# 08_PX4IO_V2.net
KiCad netlist of a schematic drawn in Altium Designer
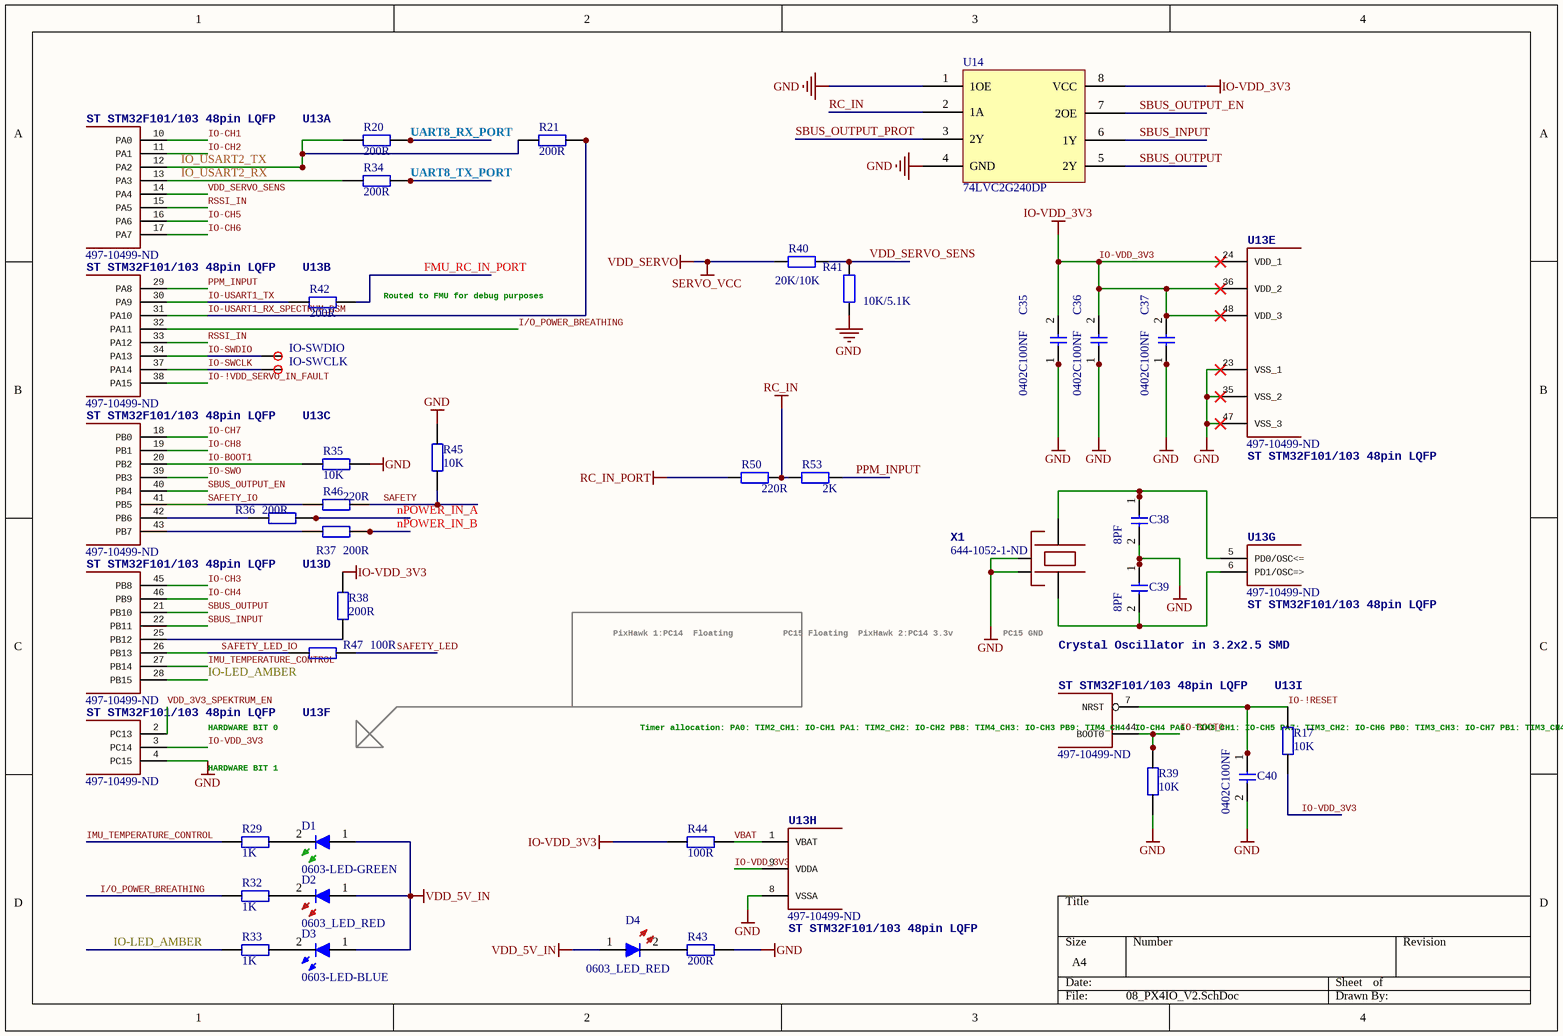
[diagram p0: 08_PX4IO_V2.SchDoc]

(export (version "E")
  (design (tool "Eeschema 10.0.6"))
  (components
    (comp (ref "C35")
      (value "0402C100NF")
      (footprint "0402C")
      (description "50V 5%")
      (libsource (lib "CUAV") (part "0402C100NF"))
    )
    (comp (ref "C36")
      (value "0402C100NF")
      (footprint "0402C")
      (description "50V 5%")
      (libsource (lib "CUAV") (part "0402C100NF"))
    )
    (comp (ref "C37")
      (value "0402C100NF")
      (footprint "0402C")
      (description "50V 5%")
      (libsource (lib "CUAV") (part "0402C100NF"))
    )
    (comp (ref "C38")
      (value "8PF")
      (footprint "0402C")
      (description "50V 5%")
      (libsource (lib "CUAV") (part "0402C100NF"))
    )
    (comp (ref "C39")
      (value "8PF")
      (footprint "0402C")
      (description "50V 5%")
      (libsource (lib "CUAV") (part "0402C100NF"))
    )
    (comp (ref "C40")
      (value "0402C100NF")
      (footprint "0402C")
      (description "50V 5%")
      (libsource (lib "CUAV") (part "0402C100NF"))
    )
    (comp (ref "D1")
      (value "0603-LED-GREEN")
      (footprint "0603-LED-Green")
      (libsource (lib "CUAV") (part "0603-LED-GREEN"))
    )
    (comp (ref "D2")
      (value "0603_LED_RED")
      (footprint "0603-LED-RED")
      (libsource (lib "CUAV") (part "0603_LED_RED"))
    )
    (comp (ref "D3")
      (value "0603-LED-BLUE")
      (footprint "0603-LED-blue")
      (libsource (lib "CUAV") (part "0603-LED-BLUE"))
    )
    (comp (ref "D4")
      (value "0603_LED_RED")
      (footprint "0603-LED-RED")
      (libsource (lib "CUAV") (part "0603_LED_RED"))
    )
    (comp (ref "IO-SWCLK")
      (value "TP_0.75")
      (footprint "TP0.75")
      (description "TP_0.75MM")
      (libsource (lib "CUAV") (part "TP_0.75"))
    )
    (comp (ref "IO-SWDIO")
      (value "TP_0.75")
      (footprint "TP0.75")
      (description "TP_0.75MM")
      (libsource (lib "CUAV") (part "TP_0.75"))
    )
    (comp (ref "R17")
      (value "10K")
      (footprint "0402R")
      (description "0402R1K 1%")
      (libsource (lib "") (part "0402R1K_3"))
    )
    (comp (ref "R20")
      (value "200R")
      (footprint "0402R")
      (description "0402R1K 1%")
      (libsource (lib "CUAV") (part "0402R1K"))
    )
    (comp (ref "R21")
      (value "200R")
      (footprint "0402R")
      (description "0402R1K 1%")
      (libsource (lib "CUAV") (part "0402R1K"))
    )
    (comp (ref "R29")
      (value "1K")
      (footprint "0402R")
      (description "0402R1K 1%")
      (libsource (lib "CUAV") (part "0402R1K"))
    )
    (comp (ref "R32")
      (value "1K")
      (footprint "0402R")
      (description "0402R1K 1%")
      (libsource (lib "CUAV") (part "0402R1K"))
    )
    (comp (ref "R33")
      (value "1K")
      (footprint "0402R")
      (description "0402R1K 1%")
      (libsource (lib "CUAV") (part "0402R1K"))
    )
    (comp (ref "R34")
      (value "200R")
      (footprint "0402R")
      (description "0402R1K 1%")
      (libsource (lib "CUAV") (part "0402R1K"))
    )
    (comp (ref "R35")
      (value "10K")
      (footprint "0402R")
      (description "0402R1K 1%")
      (libsource (lib "CUAV") (part "0402R1K"))
    )
    (comp (ref "R36")
      (value "200R")
      (footprint "0402R")
      (description "0402R1K 1%")
      (libsource (lib "CUAV") (part "0402R1K"))
    )
    (comp (ref "R37")
      (value "200R")
      (footprint "0402R")
      (description "0402R1K 1%")
      (libsource (lib "CUAV") (part "0402R1K"))
    )
    (comp (ref "R38")
      (value "200R")
      (footprint "0402R")
      (description "0402R1K 1%")
      (libsource (lib "") (part "0402R1K_2"))
    )
    (comp (ref "R39")
      (value "10K")
      (footprint "0402R")
      (description "0402R1K 1%")
      (libsource (lib "") (part "0402R1K_2"))
    )
    (comp (ref "R40")
      (value "20K/10K")
      (description "Resistor")
      (fields (field (name "PUBLISHER") "Altium Limited"))
      (libsource (lib "Miscellaneous Devices") (part "Res2"))
    )
    (comp (ref "R41")
      (value "10K/5.1K")
      (description "Resistor")
      (fields (field (name "PUBLISHER") "Altium Limited"))
      (libsource (lib "") (part "Res2_1"))
    )
    (comp (ref "R42")
      (value "200R")
      (footprint "0402R")
      (description "0402R1K 1%")
      (libsource (lib "CUAV") (part "0402R1K"))
    )
    (comp (ref "R43")
      (value "200R")
      (footprint "0402R")
      (description "0402R1K 1%")
      (libsource (lib "CUAV") (part "0402R1K"))
    )
    (comp (ref "R44")
      (value "100R")
      (footprint "0402R")
      (description "0402R1K 1%")
      (libsource (lib "CUAV") (part "0402R1K"))
    )
    (comp (ref "R45")
      (value "10K")
      (footprint "0402R")
      (description "0402R1K 1%")
      (libsource (lib "") (part "0402R1K_2"))
    )
    (comp (ref "R46")
      (value "220R")
      (footprint "0402R")
      (description "0402R1K 1%")
      (libsource (lib "") (part "0402R1K_1"))
    )
    (comp (ref "R47")
      (value "100R")
      (footprint "0402R")
      (description "0402R1K 1%")
      (libsource (lib "") (part "0402R1K_1"))
    )
    (comp (ref "R50")
      (value "220R")
      (description "Resistor")
      (fields (field (name "PUBLISHER") "Altium Limited"))
      (libsource (lib "Miscellaneous Devices") (part "Res2"))
    )
    (comp (ref "R53")
      (value "2K")
      (description "Resistor")
      (fields (field (name "PUBLISHER") "Altium Limited"))
      (libsource (lib "Miscellaneous Devices") (part "Res2"))
    )
    (comp (ref "U13")
      (value "ST STM32F101/103 48pin LQFP")
      (footprint "TQFP48")
      (description "MCU 32BIT ARM 64K FLASH 48LQFP")
      (fields (field (name "SUPPLIER PART NUMBER 1") "497-10499-ND") (field (name "3DR_PARTNO") "EMC0842"))
      (libsource (lib "pixhawk2") (part "STM32F10XCXT6"))
    )
    (comp (ref "U14")
      (value "74LVC2G240DP")
      (footprint "TSSOP8")
      (libsource (lib "hack") (part "74LVC2G240"))
    )
    (comp (ref "X1")
      (value "Crystal Oscillator in 3.2x2.5 SMD")
      (footprint "3225")
      (description "CRYSTAL 24MHZ 8PF SMD")
      (fields
        (field (name "SUPPLIER PART NUMBER 1") "644-1052-1-ND")
        (field (name "3DR_PARTNO") "ECM0708")
        (field (name "PARTNO") "NX3225SA-24.000MHZ-STD-CSR-1")
      )
      (libsource (lib "pixhawk2") (part "OSCILLATOR-3.2X2.5"))
    )
  )
  (nets
    (net (code "1") (name "/FMU_RC_IN_PORT") (class "Default")
      (node (ref "R42") (pin "2") (pintype "passive"))
    )
    (net (code "2") (name "/IMU_TEMPERATURE_CONTROL") (class "Default")
      (node (ref "R29") (pin "1") (pintype "passive"))
      (node (ref "U13") (pin "27") (pinfunction "PB14_27") (pintype "passive"))
    )
    (net (code "3") (name "/IO-!RESET") (class "Default")
      (node (ref "C40") (pin "1") (pintype "passive"))
      (node (ref "R17") (pin "1") (pintype "passive"))
      (node (ref "U13") (pin "7") (pinfunction "NRST_7") (pintype "passive"))
    )
    (net (code "4") (name "/IO-!VDD_SERVO_IN_FAULT") (class "Default")
      (node (ref "U13") (pin "38") (pinfunction "PA15_38") (pintype "passive"))
    )
    (net (code "5") (name "/IO-BOOT0") (class "Default")
      (node (ref "R39") (pin "2") (pintype "passive"))
      (node (ref "U13") (pin "44") (pinfunction "BOOT0_44") (pintype "passive"))
    )
    (net (code "6") (name "/IO-BOOT1") (class "Default")
      (node (ref "R35") (pin "1") (pintype "passive"))
      (node (ref "U13") (pin "20") (pinfunction "PB2_20") (pintype "passive"))
    )
    (net (code "7") (name "/IO-CH1") (class "Default")
      (node (ref "U13") (pin "10") (pinfunction "PA0_10") (pintype "passive"))
    )
    (net (code "8") (name "/IO-CH2") (class "Default")
      (node (ref "U13") (pin "11") (pinfunction "PA1_11") (pintype "passive"))
    )
    (net (code "9") (name "/IO-CH3") (class "Default")
      (node (ref "U13") (pin "45") (pinfunction "PB8_45") (pintype "passive"))
    )
    (net (code "10") (name "/IO-CH4") (class "Default")
      (node (ref "U13") (pin "46") (pinfunction "PB9_46") (pintype "passive"))
    )
    (net (code "11") (name "/IO-CH5") (class "Default")
      (node (ref "U13") (pin "16") (pinfunction "PA6_16") (pintype "passive"))
    )
    (net (code "12") (name "/IO-CH6") (class "Default")
      (node (ref "U13") (pin "17") (pinfunction "PA7_17") (pintype "passive"))
    )
    (net (code "13") (name "/IO-CH7") (class "Default")
      (node (ref "U13") (pin "18") (pinfunction "PB0_18") (pintype "passive"))
    )
    (net (code "14") (name "/IO-CH8") (class "Default")
      (node (ref "U13") (pin "19") (pinfunction "PB1_19") (pintype "passive"))
    )
    (net (code "15") (name "/IO-LED_AMBER") (class "Default")
      (node (ref "R33") (pin "1") (pintype "passive"))
      (node (ref "U13") (pin "28") (pinfunction "PB15_28") (pintype "passive"))
    )
    (net (code "16") (name "/IO-SWCLK") (class "Default")
      (node (ref "IO-SWCLK") (pin "0") (pintype "passive"))
      (node (ref "U13") (pin "37") (pinfunction "PA14_37") (pintype "passive"))
    )
    (net (code "17") (name "/IO-SWDIO") (class "Default")
      (node (ref "IO-SWDIO") (pin "0") (pintype "passive"))
      (node (ref "U13") (pin "34") (pinfunction "PA13_34") (pintype "passive"))
    )
    (net (code "18") (name "/IO-SWO") (class "Default")
      (node (ref "U13") (pin "39") (pinfunction "PB3_39") (pintype "passive"))
    )
    (net (code "19") (name "/IO-USART1_RX_SPECTRUM_DSM") (class "Default")
      (node (ref "R21") (pin "2") (pintype "passive"))
      (node (ref "U13") (pin "31") (pinfunction "PA10_31") (pintype "passive"))
    )
    (net (code "20") (name "/IO-USART1_TX") (class "Default")
      (node (ref "R42") (pin "1") (pintype "passive"))
      (node (ref "U13") (pin "30") (pinfunction "PA9_30") (pintype "passive"))
    )
    (net (code "21") (name "/IO_USART2_RX") (class "Default")
      (node (ref "R34") (pin "1") (pintype "passive"))
      (node (ref "U13") (pin "13") (pinfunction "PA3_13") (pintype "passive"))
    )
    (net (code "22") (name "/IO_USART2_TX") (class "Default")
      (node (ref "R20") (pin "1") (pintype "passive"))
      (node (ref "R21") (pin "1") (pintype "passive"))
      (node (ref "U13") (pin "12") (pinfunction "PA2_12") (pintype "passive"))
    )
    (net (code "23") (name "/I{slash}O_POWER_BREATHING") (class "Default")
      (node (ref "R32") (pin "1") (pintype "passive"))
      (node (ref "U13") (pin "32") (pinfunction "PA11_32") (pintype "passive"))
    )
    (net (code "24") (name "/PPM_INPUT") (class "Default")
      (node (ref "R53") (pin "2") (pinfunction "2_2") (pintype "passive"))
      (node (ref "U13") (pin "29") (pinfunction "PA8_29") (pintype "passive"))
    )
    (net (code "25") (name "/RSSI_IN") (class "Default")
      (node (ref "U13") (pin "15") (pinfunction "PA5_15") (pintype "passive"))
      (node (ref "U13") (pin "33") (pinfunction "PA12_33") (pintype "passive"))
    )
    (net (code "26") (name "/SAFETY") (class "Default")
      (node (ref "R45") (pin "1") (pintype "passive"))
      (node (ref "R46") (pin "1") (pintype "passive"))
    )
    (net (code "27") (name "/SAFETY_IO") (class "Default")
      (node (ref "R46") (pin "2") (pintype "passive"))
      (node (ref "U13") (pin "41") (pinfunction "PB5_41") (pintype "passive"))
    )
    (net (code "28") (name "/SAFETY_LED") (class "Default") (node (ref "R47") (pin "1") (pintype "passive")))
    (net (code "29") (name "/SAFETY_LED_IO") (class "Default")
      (node (ref "R47") (pin "2") (pintype "passive"))
      (node (ref "U13") (pin "26") (pinfunction "PB13_26") (pintype "passive"))
    )
    (net (code "30") (name "/SBUS_INPUT") (class "Default")
      (node (ref "U13") (pin "22") (pinfunction "PB11_22") (pintype "passive"))
      (node (ref "U14") (pin "6") (pinfunction "1Y_6") (pintype "passive"))
    )
    (net (code "31") (name "/SBUS_OUTPUT") (class "Default")
      (node (ref "U13") (pin "21") (pinfunction "PB10_21") (pintype "passive"))
      (node (ref "U14") (pin "5") (pinfunction "2Y_5") (pintype "passive"))
    )
    (net (code "32") (name "/SBUS_OUTPUT_EN") (class "Default")
      (node (ref "U13") (pin "40") (pinfunction "PB4_40") (pintype "passive"))
      (node (ref "U14") (pin "7") (pinfunction "2OE_7") (pintype "passive"))
    )
    (net (code "33") (name "/SBUS_OUTPUT_PROT") (class "Default")
      (node (ref "U14") (pin "3") (pinfunction "2Y_3") (pintype "passive"))
    )
    (net (code "34") (name "/UART8_RX_PORT") (class "Default")
      (node (ref "R20") (pin "2") (pintype "passive"))
    )
    (net (code "35") (name "/UART8_TX_PORT") (class "Default")
      (node (ref "R34") (pin "2") (pintype "passive"))
    )
    (net (code "36") (name "/VBAT") (class "Default")
      (node (ref "R44") (pin "2") (pintype "passive"))
      (node (ref "U13") (pin "1") (pinfunction "VBAT_1") (pintype "power_in"))
    )
    (net (code "37") (name "/VDD_3V3_SPEKTRUM_EN") (class "Default")
      (node (ref "U13") (pin "2") (pinfunction "PC13_2") (pintype "passive"))
    )
    (net (code "38") (name "/VDD_SERVO_SENS") (class "Default")
      (node (ref "R40") (pin "2") (pinfunction "2_2") (pintype "passive"))
      (node (ref "R41") (pin "2") (pinfunction "2_2") (pintype "passive"))
      (node (ref "U13") (pin "14") (pinfunction "PA4_14") (pintype "passive"))
    )
    (net (code "39") (name "/nPOWER_IN_A") (class "Default") (node (ref "R36") (pin "2") (pintype "passive")))
    (net (code "40") (name "/nPOWER_IN_B") (class "Default") (node (ref "R37") (pin "2") (pintype "passive")))
    (net (code "41") (name "GND") (class "Default")
      (node (ref "C35") (pin "1") (pintype "passive"))
      (node (ref "C36") (pin "1") (pintype "passive"))
      (node (ref "C37") (pin "1") (pintype "passive"))
      (node (ref "C38") (pin "2") (pintype "passive"))
      (node (ref "C39") (pin "1") (pintype "passive"))
      (node (ref "C40") (pin "2") (pintype "passive"))
      (node (ref "R35") (pin "2") (pintype "passive"))
      (node (ref "R39") (pin "1") (pintype "passive"))
      (node (ref "R41") (pin "1") (pinfunction "1_1") (pintype "passive"))
      (node (ref "R43") (pin "2") (pintype "passive"))
      (node (ref "R45") (pin "2") (pintype "passive"))
      (node (ref "U13") (pin "23") (pinfunction "VSS_1_23") (pintype "power_in"))
      (node (ref "U13") (pin "35") (pinfunction "VSS_2_35") (pintype "power_in"))
      (node (ref "U13") (pin "4") (pinfunction "PC15_4") (pintype "passive"))
      (node (ref "U13") (pin "47") (pinfunction "VSS_3_47") (pintype "power_in"))
      (node (ref "U13") (pin "8") (pinfunction "VSSA_8") (pintype "power_in"))
      (node (ref "U14") (pin "1") (pinfunction "1OE_1") (pintype "passive"))
      (node (ref "U14") (pin "4") (pinfunction "GND_4") (pintype "passive"))
      (node (ref "X1") (pin "2") (pinfunction "NC_2_2") (pintype "open_emitter"))
      (node (ref "X1") (pin "4") (pinfunction "NC_4_4") (pintype "open_emitter"))
    )
    (net (code "42") (name "IO-VDD_3V3") (class "Default")
      (node (ref "C35") (pin "2") (pintype "passive"))
      (node (ref "C36") (pin "2") (pintype "passive"))
      (node (ref "C37") (pin "2") (pintype "passive"))
      (node (ref "R17") (pin "2") (pintype "passive"))
      (node (ref "R38") (pin "2") (pintype "passive"))
      (node (ref "R44") (pin "1") (pintype "passive"))
      (node (ref "U13") (pin "24") (pinfunction "VDD_1_24") (pintype "power_in"))
      (node (ref "U13") (pin "3") (pinfunction "PC14_3") (pintype "passive"))
      (node (ref "U13") (pin "36") (pinfunction "VDD_2_36") (pintype "power_in"))
      (node (ref "U13") (pin "48") (pinfunction "VDD_3_48") (pintype "power_in"))
      (node (ref "U13") (pin "9") (pinfunction "VDDA_9") (pintype "power_in"))
      (node (ref "U14") (pin "8") (pinfunction "VCC_8") (pintype "passive"))
    )
    (net (code "43") (name "Net-(D1-Pad2)") (class "Default")
      (node (ref "D1") (pin "2") (pintype "passive"))
      (node (ref "R29") (pin "2") (pintype "passive"))
    )
    (net (code "44") (name "Net-(D2-Pad2)") (class "Default")
      (node (ref "D2") (pin "2") (pintype "passive"))
      (node (ref "R32") (pin "2") (pintype "passive"))
    )
    (net (code "45") (name "Net-(D3-Pad2)") (class "Default")
      (node (ref "D3") (pin "2") (pintype "passive"))
      (node (ref "R33") (pin "2") (pintype "passive"))
    )
    (net (code "46") (name "Net-(D4-Pad2)") (class "Default")
      (node (ref "D4") (pin "2") (pintype "passive"))
      (node (ref "R43") (pin "1") (pintype "passive"))
    )
    (net (code "47") (name "Net-(U13C-PB6)") (class "Default")
      (node (ref "R36") (pin "1") (pintype "passive"))
      (node (ref "U13") (pin "42") (pinfunction "PB6_42") (pintype "passive"))
    )
    (net (code "48") (name "Net-(U13C-PB7)") (class "Default")
      (node (ref "R37") (pin "1") (pintype "passive"))
      (node (ref "U13") (pin "43") (pinfunction "PB7_43") (pintype "passive"))
    )
    (net (code "49") (name "Net-(U13D-PB12)") (class "Default")
      (node (ref "R38") (pin "1") (pintype "passive"))
      (node (ref "U13") (pin "25") (pinfunction "PB12_25") (pintype "passive"))
    )
    (net (code "50") (name "Net-(U13G-PD0{slash}OSC<=)") (class "Default")
      (node (ref "C38") (pin "1") (pintype "passive"))
      (node (ref "U13") (pin "5") (pinfunction "PD0/OSC<=_5") (pintype "passive"))
      (node (ref "X1") (pin "3") (pinfunction "3_3") (pintype "passive"))
    )
    (net (code "51") (name "Net-(U13G-PD1{slash}OSC=>)") (class "Default")
      (node (ref "C39") (pin "2") (pintype "passive"))
      (node (ref "U13") (pin "6") (pinfunction "PD1/OSC=>_6") (pintype "passive"))
      (node (ref "X1") (pin "1") (pinfunction "1_1") (pintype "passive"))
    )
    (net (code "52") (name "RC_IN") (class "Default")
      (node (ref "R50") (pin "2") (pinfunction "2_2") (pintype "passive"))
      (node (ref "R53") (pin "1") (pinfunction "1_1") (pintype "passive"))
      (node (ref "U14") (pin "2") (pinfunction "1A_2") (pintype "passive"))
    )
    (net (code "53") (name "RC_IN_PORT") (class "Default")
      (node (ref "R50") (pin "1") (pinfunction "1_1") (pintype "passive"))
    )
    (net (code "54") (name "SERVO_VCC") (class "Default")
      (node (ref "R40") (pin "1") (pinfunction "1_1") (pintype "passive"))
    )
    (net (code "55") (name "VDD_5V_IN") (class "Default")
      (node (ref "D1") (pin "1") (pintype "passive"))
      (node (ref "D2") (pin "1") (pintype "passive"))
      (node (ref "D3") (pin "1") (pintype "passive"))
      (node (ref "D4") (pin "1") (pintype "passive"))
    )
  )
)
